# Sheet5.net
KiCad netlist of a schematic drawn in Altium Designer
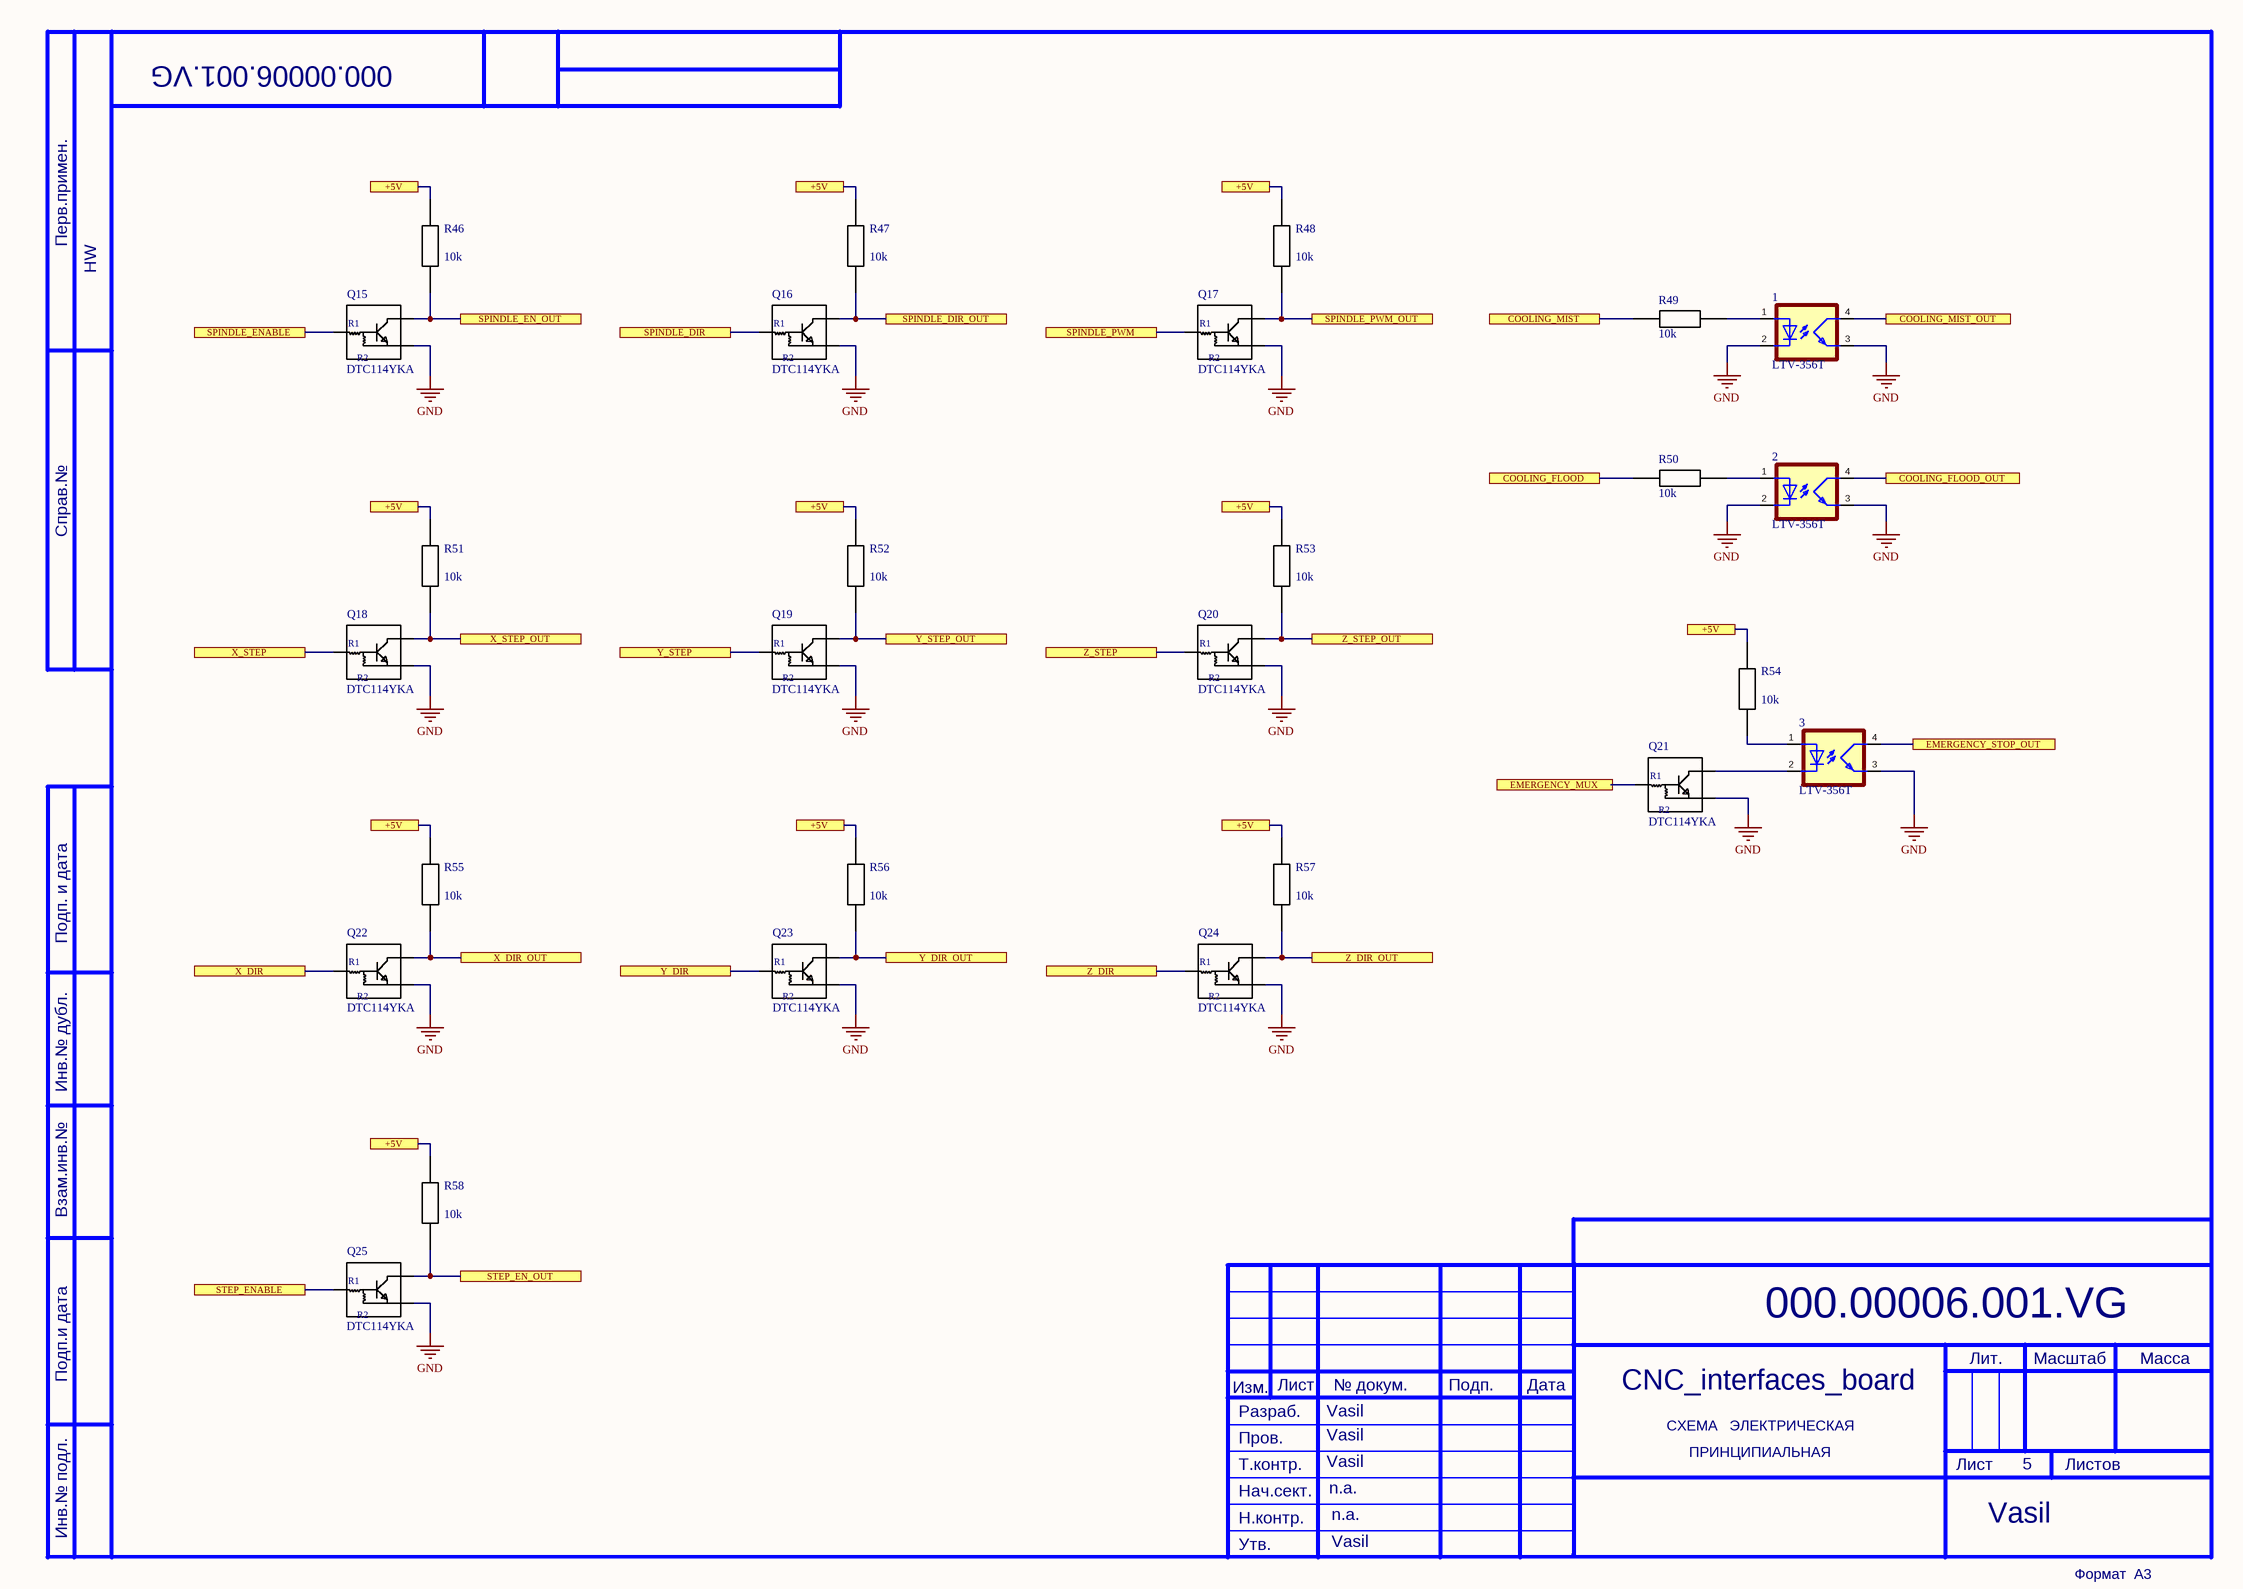
[diagram p0: Sheet5.SchDoc]

(export (version "E")
  (design (tool "Eeschema 10.0.6"))
  (components
    (comp (ref "1")
      (value "LTV-356T")
      (footprint "MINI-FLAT-4")
      (description "Optoisolator Transistor Output 3750Vrms 1 Channel 4-SOP")
      (fields (field (name "MF") "Lite-On Inc."))
      (libsource (lib "CAN_Library") (part "LTV-356T"))
    )
    (comp (ref "2")
      (value "LTV-356T")
      (footprint "MINI-FLAT-4")
      (description "Optoisolator Transistor Output 3750Vrms 1 Channel 4-SOP")
      (fields (field (name "MF") "Lite-On Inc."))
      (libsource (lib "CAN_Library") (part "LTV-356T"))
    )
    (comp (ref "3")
      (value "LTV-356T")
      (footprint "MINI-FLAT-4")
      (description "Optoisolator Transistor Output 3750Vrms 1 Channel 4-SOP")
      (fields (field (name "MF") "Lite-On Inc."))
      (libsource (lib "CAN_Library") (part "LTV-356T"))
    )
    (comp (ref "Q15")
      (value "DTC114YKA")
      (footprint "SOT-346 (SC59) Black")
      (description "NPN Digital 50V 100mA 200mW  R1=10kOm R2=47kOm")
      (fields (field (name "MANUFACTURER") "ROHM Semiconductor"))
      (libsource (lib "CAN_Library") (part "DTC114YKA"))
    )
    (comp (ref "Q16")
      (value "DTC114YKA")
      (footprint "SOT-346 (SC59) Black")
      (description "NPN Digital 50V 100mA 200mW  R1=10kOm R2=47kOm")
      (fields (field (name "MANUFACTURER") "ROHM Semiconductor"))
      (libsource (lib "CAN_Library") (part "DTC114YKA"))
    )
    (comp (ref "Q17")
      (value "DTC114YKA")
      (footprint "SOT-346 (SC59) Black")
      (description "NPN Digital 50V 100mA 200mW  R1=10kOm R2=47kOm")
      (fields (field (name "MANUFACTURER") "ROHM Semiconductor"))
      (libsource (lib "CAN_Library") (part "DTC114YKA"))
    )
    (comp (ref "Q18")
      (value "DTC114YKA")
      (footprint "SOT-346 (SC59) Black")
      (description "NPN Digital 50V 100mA 200mW  R1=10kOm R2=47kOm")
      (fields (field (name "MANUFACTURER") "ROHM Semiconductor"))
      (libsource (lib "CAN_Library") (part "DTC114YKA"))
    )
    (comp (ref "Q19")
      (value "DTC114YKA")
      (footprint "SOT-346 (SC59) Black")
      (description "NPN Digital 50V 100mA 200mW  R1=10kOm R2=47kOm")
      (fields (field (name "MANUFACTURER") "ROHM Semiconductor"))
      (libsource (lib "CAN_Library") (part "DTC114YKA"))
    )
    (comp (ref "Q20")
      (value "DTC114YKA")
      (footprint "SOT-346 (SC59) Black")
      (description "NPN Digital 50V 100mA 200mW  R1=10kOm R2=47kOm")
      (fields (field (name "MANUFACTURER") "ROHM Semiconductor"))
      (libsource (lib "CAN_Library") (part "DTC114YKA"))
    )
    (comp (ref "Q21")
      (value "DTC114YKA")
      (footprint "SOT-346 (SC59) Black")
      (description "NPN Digital 50V 100mA 200mW  R1=10kOm R2=47kOm")
      (fields (field (name "MANUFACTURER") "ROHM Semiconductor"))
      (libsource (lib "CAN_Library") (part "DTC114YKA"))
    )
    (comp (ref "Q22")
      (value "DTC114YKA")
      (footprint "SOT-346 (SC59) Black")
      (description "NPN Digital 50V 100mA 200mW  R1=10kOm R2=47kOm")
      (fields (field (name "MANUFACTURER") "ROHM Semiconductor"))
      (libsource (lib "CAN_Library") (part "DTC114YKA"))
    )
    (comp (ref "Q23")
      (value "DTC114YKA")
      (footprint "SOT-346 (SC59) Black")
      (description "NPN Digital 50V 100mA 200mW  R1=10kOm R2=47kOm")
      (fields (field (name "MANUFACTURER") "ROHM Semiconductor"))
      (libsource (lib "CAN_Library") (part "DTC114YKA"))
    )
    (comp (ref "Q24")
      (value "DTC114YKA")
      (footprint "SOT-346 (SC59) Black")
      (description "NPN Digital 50V 100mA 200mW  R1=10kOm R2=47kOm")
      (fields (field (name "MANUFACTURER") "ROHM Semiconductor"))
      (libsource (lib "CAN_Library") (part "DTC114YKA"))
    )
    (comp (ref "Q25")
      (value "DTC114YKA")
      (footprint "SOT-346 (SC59) Black")
      (description "NPN Digital 50V 100mA 200mW  R1=10kOm R2=47kOm")
      (fields (field (name "MANUFACTURER") "ROHM Semiconductor"))
      (libsource (lib "CAN_Library") (part "DTC114YKA"))
    )
    (comp (ref "R46")
      (value "10k")
      (footprint "SMD 0805")
      (description "RES")
      (libsource (lib "CAN_Library") (part "Resistor_1"))
    )
    (comp (ref "R47")
      (value "10k")
      (footprint "SMD 0805")
      (description "RES")
      (libsource (lib "CAN_Library") (part "Resistor_1"))
    )
    (comp (ref "R48")
      (value "10k")
      (footprint "SMD 0805")
      (description "RES")
      (libsource (lib "CAN_Library") (part "Resistor_1"))
    )
    (comp (ref "R49")
      (value "10k")
      (footprint "SMD 0805")
      (description "RES")
      (libsource (lib "CAN_Library") (part "Resistor_1"))
    )
    (comp (ref "R50")
      (value "10k")
      (footprint "SMD 0805")
      (description "RES")
      (libsource (lib "CAN_Library") (part "Resistor_1"))
    )
    (comp (ref "R51")
      (value "10k")
      (footprint "SMD 0805")
      (description "RES")
      (libsource (lib "CAN_Library") (part "Resistor_1"))
    )
    (comp (ref "R52")
      (value "10k")
      (footprint "SMD 0805")
      (description "RES")
      (libsource (lib "CAN_Library") (part "Resistor_1"))
    )
    (comp (ref "R53")
      (value "10k")
      (footprint "SMD 0805")
      (description "RES")
      (libsource (lib "CAN_Library") (part "Resistor_1"))
    )
    (comp (ref "R54")
      (value "10k")
      (footprint "SMD 0805")
      (description "RES")
      (libsource (lib "CAN_Library") (part "Resistor_1"))
    )
    (comp (ref "R55")
      (value "10k")
      (footprint "SMD 0805")
      (description "RES")
      (libsource (lib "CAN_Library") (part "Resistor_1"))
    )
    (comp (ref "R56")
      (value "10k")
      (footprint "SMD 0805")
      (description "RES")
      (libsource (lib "CAN_Library") (part "Resistor_1"))
    )
    (comp (ref "R57")
      (value "10k")
      (footprint "SMD 0805")
      (description "RES")
      (libsource (lib "CAN_Library") (part "Resistor_1"))
    )
    (comp (ref "R58")
      (value "10k")
      (footprint "SMD 0805")
      (description "RES")
      (libsource (lib "CAN_Library") (part "Resistor_1"))
    )
  )
  (nets
    (net (code "1") (name "/+5V") (class "Default")
      (node (ref "R46") (pin "1") (pinfunction "1_1") (pintype "passive"))
      (node (ref "R47") (pin "1") (pinfunction "1_1") (pintype "passive"))
      (node (ref "R48") (pin "1") (pinfunction "1_1") (pintype "passive"))
      (node (ref "R51") (pin "1") (pinfunction "1_1") (pintype "passive"))
      (node (ref "R52") (pin "1") (pinfunction "1_1") (pintype "passive"))
      (node (ref "R53") (pin "1") (pinfunction "1_1") (pintype "passive"))
      (node (ref "R54") (pin "1") (pinfunction "1_1") (pintype "passive"))
      (node (ref "R55") (pin "1") (pinfunction "1_1") (pintype "passive"))
      (node (ref "R56") (pin "1") (pinfunction "1_1") (pintype "passive"))
      (node (ref "R57") (pin "1") (pinfunction "1_1") (pintype "passive"))
      (node (ref "R58") (pin "1") (pinfunction "1_1") (pintype "passive"))
    )
    (net (code "2") (name "/COOLING_FLOOD") (class "Default")
      (node (ref "R50") (pin "1") (pinfunction "1_1") (pintype "passive"))
    )
    (net (code "3") (name "/COOLING_FLOOD_OUT") (class "Default")
      (node (ref "2") (pin "4") (pinfunction "COL_4") (pintype "passive"))
    )
    (net (code "4") (name "/COOLING_MIST") (class "Default")
      (node (ref "R49") (pin "1") (pinfunction "1_1") (pintype "passive"))
    )
    (net (code "5") (name "/COOLING_MIST_OUT") (class "Default")
      (node (ref "1") (pin "4") (pinfunction "COL_4") (pintype "passive"))
    )
    (net (code "6") (name "/EMERGENCY_MUX") (class "Default")
      (node (ref "Q21") (pin "1") (pinfunction "1_1") (pintype "passive"))
    )
    (net (code "7") (name "/EMERGENCY_STOP_OUT") (class "Default")
      (node (ref "3") (pin "4") (pinfunction "COL_4") (pintype "passive"))
    )
    (net (code "8") (name "/SPINDLE_DIR") (class "Default")
      (node (ref "Q16") (pin "1") (pinfunction "1_1") (pintype "passive"))
    )
    (net (code "9") (name "/SPINDLE_DIR_OUT") (class "Default")
      (node (ref "Q16") (pin "3") (pinfunction "3_3") (pintype "passive"))
      (node (ref "R47") (pin "2") (pinfunction "2_2") (pintype "passive"))
    )
    (net (code "10") (name "/SPINDLE_ENABLE") (class "Default")
      (node (ref "Q15") (pin "1") (pinfunction "1_1") (pintype "passive"))
    )
    (net (code "11") (name "/SPINDLE_EN_OUT") (class "Default")
      (node (ref "Q15") (pin "3") (pinfunction "3_3") (pintype "passive"))
      (node (ref "R46") (pin "2") (pinfunction "2_2") (pintype "passive"))
    )
    (net (code "12") (name "/SPINDLE_PWM") (class "Default")
      (node (ref "Q17") (pin "1") (pinfunction "1_1") (pintype "passive"))
    )
    (net (code "13") (name "/SPINDLE_PWM_OUT") (class "Default")
      (node (ref "Q17") (pin "3") (pinfunction "3_3") (pintype "passive"))
      (node (ref "R48") (pin "2") (pinfunction "2_2") (pintype "passive"))
    )
    (net (code "14") (name "/STEP_ENABLE") (class "Default")
      (node (ref "Q25") (pin "1") (pinfunction "1_1") (pintype "passive"))
    )
    (net (code "15") (name "/STEP_EN_OUT") (class "Default")
      (node (ref "Q25") (pin "3") (pinfunction "3_3") (pintype "passive"))
      (node (ref "R58") (pin "2") (pinfunction "2_2") (pintype "passive"))
    )
    (net (code "16") (name "/X_DIR") (class "Default")
      (node (ref "Q22") (pin "1") (pinfunction "1_1") (pintype "passive"))
    )
    (net (code "17") (name "/X_DIR_OUT") (class "Default")
      (node (ref "Q22") (pin "3") (pinfunction "3_3") (pintype "passive"))
      (node (ref "R55") (pin "2") (pinfunction "2_2") (pintype "passive"))
    )
    (net (code "18") (name "/X_STEP") (class "Default")
      (node (ref "Q18") (pin "1") (pinfunction "1_1") (pintype "passive"))
    )
    (net (code "19") (name "/X_STEP_OUT") (class "Default")
      (node (ref "Q18") (pin "3") (pinfunction "3_3") (pintype "passive"))
      (node (ref "R51") (pin "2") (pinfunction "2_2") (pintype "passive"))
    )
    (net (code "20") (name "/Y_DIR") (class "Default")
      (node (ref "Q23") (pin "1") (pinfunction "1_1") (pintype "passive"))
    )
    (net (code "21") (name "/Y_DIR_OUT") (class "Default")
      (node (ref "Q23") (pin "3") (pinfunction "3_3") (pintype "passive"))
      (node (ref "R56") (pin "2") (pinfunction "2_2") (pintype "passive"))
    )
    (net (code "22") (name "/Y_STEP") (class "Default")
      (node (ref "Q19") (pin "1") (pinfunction "1_1") (pintype "passive"))
    )
    (net (code "23") (name "/Y_STEP_OUT") (class "Default")
      (node (ref "Q19") (pin "3") (pinfunction "3_3") (pintype "passive"))
      (node (ref "R52") (pin "2") (pinfunction "2_2") (pintype "passive"))
    )
    (net (code "24") (name "/Z_DIR") (class "Default")
      (node (ref "Q24") (pin "1") (pinfunction "1_1") (pintype "passive"))
    )
    (net (code "25") (name "/Z_DIR_OUT") (class "Default")
      (node (ref "Q24") (pin "3") (pinfunction "3_3") (pintype "passive"))
      (node (ref "R57") (pin "2") (pinfunction "2_2") (pintype "passive"))
    )
    (net (code "26") (name "/Z_STEP") (class "Default")
      (node (ref "Q20") (pin "1") (pinfunction "1_1") (pintype "passive"))
    )
    (net (code "27") (name "/Z_STEP_OUT") (class "Default")
      (node (ref "Q20") (pin "3") (pinfunction "3_3") (pintype "passive"))
      (node (ref "R53") (pin "2") (pinfunction "2_2") (pintype "passive"))
    )
    (net (code "28") (name "GND") (class "Default")
      (node (ref "1") (pin "2") (pinfunction "C_2") (pintype "passive"))
      (node (ref "1") (pin "3") (pinfunction "EMIT_3") (pintype "passive"))
      (node (ref "2") (pin "2") (pinfunction "C_2") (pintype "passive"))
      (node (ref "2") (pin "3") (pinfunction "EMIT_3") (pintype "passive"))
      (node (ref "3") (pin "3") (pinfunction "EMIT_3") (pintype "passive"))
      (node (ref "Q15") (pin "2") (pinfunction "2_2") (pintype "passive"))
      (node (ref "Q16") (pin "2") (pinfunction "2_2") (pintype "passive"))
      (node (ref "Q17") (pin "2") (pinfunction "2_2") (pintype "passive"))
      (node (ref "Q18") (pin "2") (pinfunction "2_2") (pintype "passive"))
      (node (ref "Q19") (pin "2") (pinfunction "2_2") (pintype "passive"))
      (node (ref "Q20") (pin "2") (pinfunction "2_2") (pintype "passive"))
      (node (ref "Q21") (pin "2") (pinfunction "2_2") (pintype "passive"))
      (node (ref "Q22") (pin "2") (pinfunction "2_2") (pintype "passive"))
      (node (ref "Q23") (pin "2") (pinfunction "2_2") (pintype "passive"))
      (node (ref "Q24") (pin "2") (pinfunction "2_2") (pintype "passive"))
      (node (ref "Q25") (pin "2") (pinfunction "2_2") (pintype "passive"))
    )
    (net (code "29") (name "Net-(1-A)") (class "Default")
      (node (ref "1") (pin "1") (pinfunction "A_1") (pintype "passive"))
      (node (ref "R49") (pin "2") (pinfunction "2_2") (pintype "passive"))
    )
    (net (code "30") (name "Net-(2-A)") (class "Default")
      (node (ref "2") (pin "1") (pinfunction "A_1") (pintype "passive"))
      (node (ref "R50") (pin "2") (pinfunction "2_2") (pintype "passive"))
    )
    (net (code "31") (name "Net-(3-A)") (class "Default")
      (node (ref "3") (pin "1") (pinfunction "A_1") (pintype "passive"))
      (node (ref "R54") (pin "2") (pinfunction "2_2") (pintype "passive"))
    )
    (net (code "32") (name "Net-(3-C)") (class "Default")
      (node (ref "3") (pin "2") (pinfunction "C_2") (pintype "passive"))
      (node (ref "Q21") (pin "3") (pinfunction "3_3") (pintype "passive"))
    )
  )
)
